# Sidekick_Breakout_V1_2_LDO.net
KiCad netlist of a schematic drawn in EasyEDA
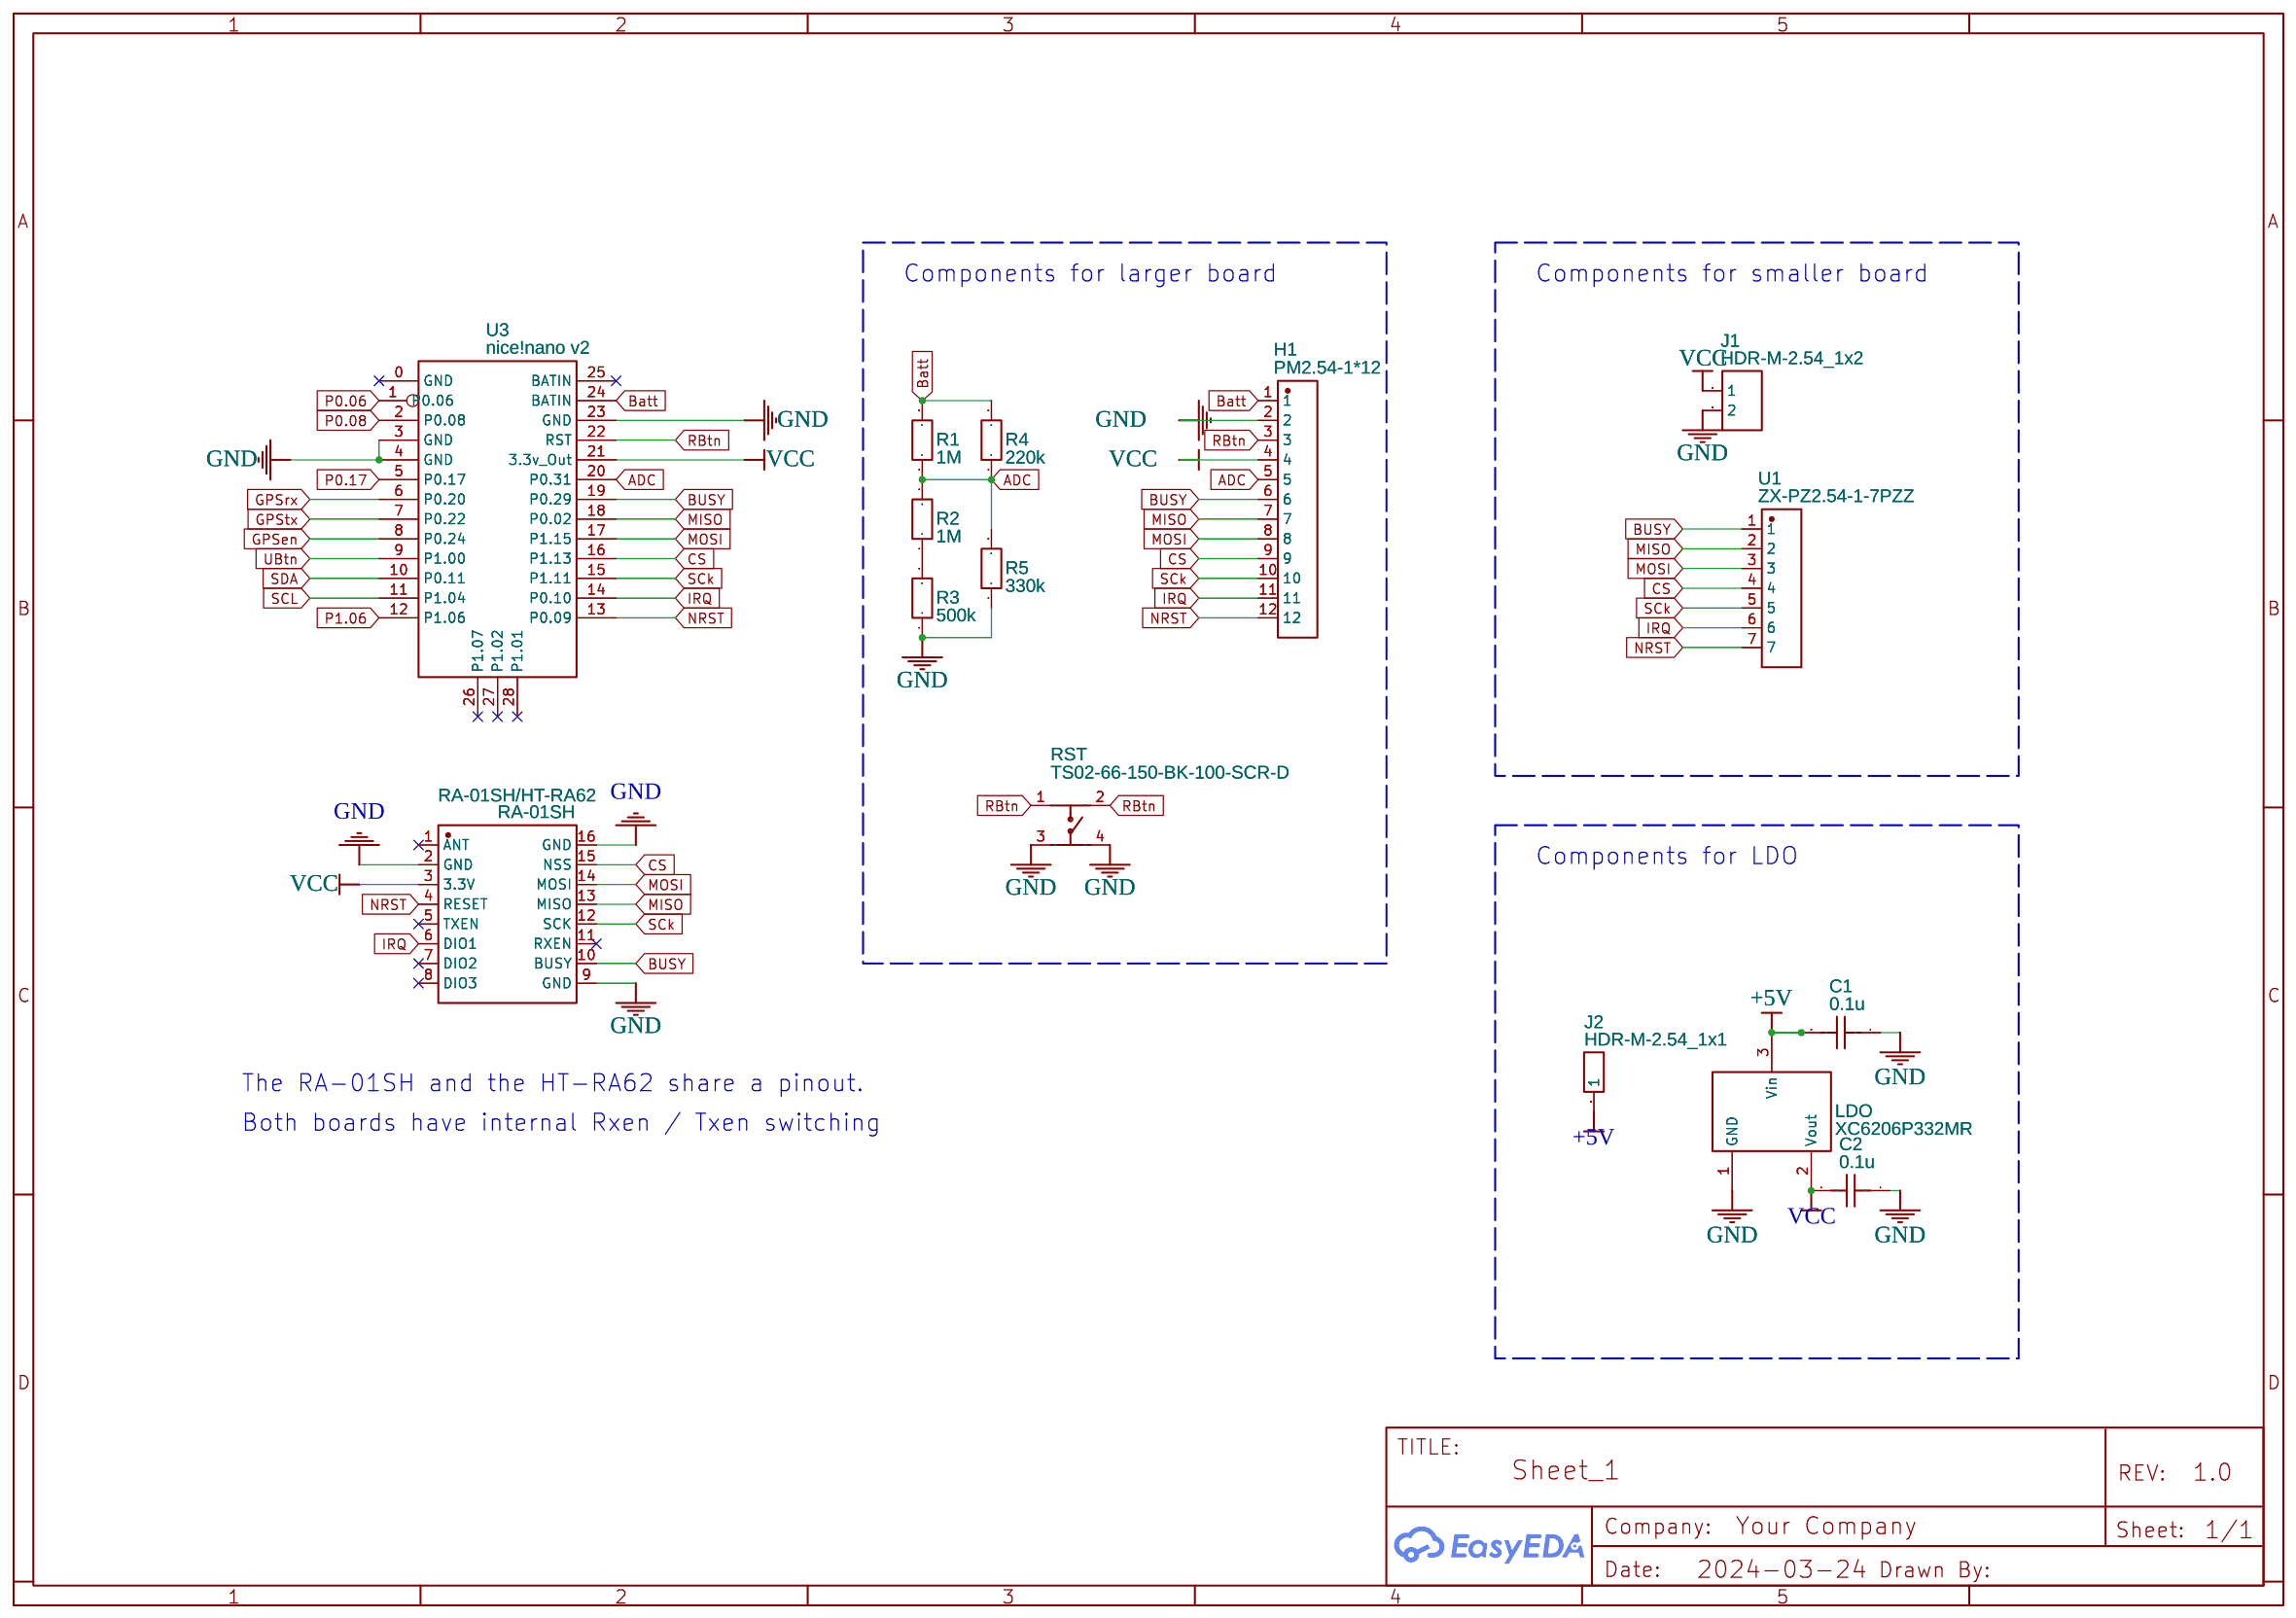
[diagram p0: schematic sheet]

(export (version "E")
  (design (tool "Eeschema 10.0.6"))
  (components
    (comp (ref "C1") (value "0.1u") (libsource (lib "") (part "C_0805_US")))
    (comp (ref "C2") (value "0.1u") (libsource (lib "") (part "C_0805_US")))
    (comp (ref "H1")
      (value "PM2.54-1*12")
      (fields (field (name "Manufacturer") "ZHOURI(洲日)"))
      (libsource (lib "") (part "PM2.54-1*12"))
    )
    (comp (ref "J1") (value "HDR-M-2.54_1x2") (libsource (lib "") (part "HDR-M-2.54_1x2")))
    (comp (ref "J2") (value "HDR-M-2.54_1x1") (libsource (lib "") (part "HDR-M-2.54_1x1")))
    (comp (ref "LDO")
      (value "XC6206P332MR")
      (fields (field (name "Manufacturer Part") "XC6206P332MR-G") (field (name "Manufacturer") "TOREX(特瑞仕)"))
      (libsource (lib "") (part "XC6206P332MR"))
    )
    (comp (ref "R1") (value "1M") (libsource (lib "") (part "R_1206_EU")))
    (comp (ref "R2") (value "1M") (libsource (lib "") (part "R_1206_EU")))
    (comp (ref "R3") (value "500k") (libsource (lib "") (part "R_1206_EU")))
    (comp (ref "R4") (value "220k") (libsource (lib "") (part "R_AXIAL-0.3_EU")))
    (comp (ref "R5") (value "330k") (libsource (lib "") (part "R_AXIAL-0.3_EU")))
    (comp (ref "RA-01SH/HT-RA62")
      (value "RA-01SH")
      (fields (field (name "Manufacturer Part") "Ra-01SH") (field (name "Manufacturer") "Ai-Thinker(安信可)"))
      (libsource (lib "") (part "RA-01SH"))
    )
    (comp (ref "RST")
      (value "TS02-66-150-BK-100-SCR-D")
      (fields (field (name "Manufacturer") "CUI"))
      (libsource (lib "") (part "TS02-66-150-BK-100-SCR-D"))
    )
    (comp (ref "U1")
      (value "ZX-PZ2.54-1-7PZZ")
      (fields (field (name "Manufacturer") "Megastar(兆星)"))
      (libsource (lib "") (part "ZX-PZ2.54-1-7PZZ"))
    )
    (comp (ref "U3")
      (value "nice!nano v2")
      (fields (field (name "Manufacturer") "nice!"))
      (libsource (lib "") (part "nice!nano v2"))
    )
  )
  (nets
    (net (code "1") (name "+5V") (class "Default")
      (node (ref "C1") (pin "2") (pinfunction "2_2") (pintype "unspecified"))
      (node (ref "J2") (pin "1") (pinfunction "1_1") (pintype "input"))
      (node (ref "LDO") (pin "3") (pinfunction "Vin_3") (pintype "unspecified"))
    )
    (net (code "2") (name "ADC") (class "Default")
      (node (ref "H1") (pin "5") (pinfunction "5_5") (pintype "unspecified"))
      (node (ref "R1") (pin "1") (pinfunction "1_1") (pintype "unspecified"))
      (node (ref "R2") (pin "2") (pinfunction "2_2") (pintype "unspecified"))
      (node (ref "R4") (pin "1") (pinfunction "1_1") (pintype "unspecified"))
      (node (ref "R5") (pin "2") (pinfunction "2_2") (pintype "unspecified"))
      (node (ref "U3") (pin "20") (pinfunction "P0.31_20") (pintype "bidirectional"))
    )
    (net (code "3") (name "BUSY") (class "Default")
      (node (ref "H1") (pin "6") (pinfunction "6_6") (pintype "unspecified"))
      (node (ref "RA-01SH/HT-RA62") (pin "10") (pinfunction "BUSY_10") (pintype "unspecified"))
      (node (ref "U1") (pin "1") (pinfunction "1_1") (pintype "unspecified"))
      (node (ref "U3") (pin "19") (pinfunction "P0.29_19") (pintype "bidirectional"))
    )
    (net (code "4") (name "Batt") (class "Default")
      (node (ref "H1") (pin "1") (pinfunction "1_1") (pintype "unspecified"))
      (node (ref "R1") (pin "2") (pinfunction "2_2") (pintype "unspecified"))
      (node (ref "R4") (pin "2") (pinfunction "2_2") (pintype "unspecified"))
      (node (ref "U3") (pin "24") (pinfunction "BATIN_24") (pintype "bidirectional"))
    )
    (net (code "5") (name "CS") (class "Default")
      (node (ref "H1") (pin "9") (pinfunction "9_9") (pintype "unspecified"))
      (node (ref "RA-01SH/HT-RA62") (pin "15") (pinfunction "NSS_15") (pintype "unspecified"))
      (node (ref "U1") (pin "4") (pinfunction "4_4") (pintype "unspecified"))
      (node (ref "U3") (pin "16") (pinfunction "P1.13_16") (pintype "bidirectional"))
    )
    (net (code "6") (name "GND") (class "Default")
      (node (ref "C1") (pin "1") (pinfunction "1_1") (pintype "unspecified"))
      (node (ref "C2") (pin "1") (pinfunction "1_1") (pintype "unspecified"))
      (node (ref "H1") (pin "2") (pinfunction "2_2") (pintype "unspecified"))
      (node (ref "J1") (pin "2") (pinfunction "2_2") (pintype "unspecified"))
      (node (ref "LDO") (pin "1") (pinfunction "GND_1") (pintype "unspecified"))
      (node (ref "R3") (pin "1") (pinfunction "1_1") (pintype "unspecified"))
      (node (ref "R5") (pin "1") (pinfunction "1_1") (pintype "unspecified"))
      (node (ref "RA-01SH/HT-RA62") (pin "16") (pinfunction "GND_16") (pintype "unspecified"))
      (node (ref "RA-01SH/HT-RA62") (pin "2") (pinfunction "GND_2") (pintype "unspecified"))
      (node (ref "RA-01SH/HT-RA62") (pin "9") (pinfunction "GND_9") (pintype "unspecified"))
      (node (ref "RST") (pin "3") (pinfunction "3_3") (pintype "unspecified"))
      (node (ref "RST") (pin "4") (pinfunction "4_4") (pintype "unspecified"))
      (node (ref "U3") (pin "23") (pinfunction "GND_23") (pintype "bidirectional"))
      (node (ref "U3") (pin "3") (pinfunction "GND_3") (pintype "unspecified"))
      (node (ref "U3") (pin "4") (pinfunction "GND_4") (pintype "unspecified"))
    )
    (net (code "7") (name "GPSen") (class "Default")
      (node (ref "U3") (pin "8") (pinfunction "P0.24_8") (pintype "unspecified"))
    )
    (net (code "8") (name "GPSrx") (class "Default")
      (node (ref "U3") (pin "6") (pinfunction "P0.20_6") (pintype "unspecified"))
    )
    (net (code "9") (name "GPStx") (class "Default")
      (node (ref "U3") (pin "7") (pinfunction "P0.22_7") (pintype "unspecified"))
    )
    (net (code "10") (name "IRQ") (class "Default")
      (node (ref "H1") (pin "11") (pinfunction "11_11") (pintype "unspecified"))
      (node (ref "RA-01SH/HT-RA62") (pin "6") (pinfunction "DIO1_6") (pintype "unspecified"))
      (node (ref "U1") (pin "6") (pinfunction "6_6") (pintype "unspecified"))
      (node (ref "U3") (pin "14") (pinfunction "P0.10_14") (pintype "bidirectional"))
    )
    (net (code "11") (name "MISO") (class "Default")
      (node (ref "H1") (pin "7") (pinfunction "7_7") (pintype "unspecified"))
      (node (ref "RA-01SH/HT-RA62") (pin "13") (pinfunction "MISO_13") (pintype "unspecified"))
      (node (ref "U1") (pin "2") (pinfunction "2_2") (pintype "unspecified"))
      (node (ref "U3") (pin "18") (pinfunction "P0.02_18") (pintype "bidirectional"))
    )
    (net (code "12") (name "MOSI") (class "Default")
      (node (ref "H1") (pin "8") (pinfunction "8_8") (pintype "unspecified"))
      (node (ref "RA-01SH/HT-RA62") (pin "14") (pinfunction "MOSI_14") (pintype "unspecified"))
      (node (ref "U1") (pin "3") (pinfunction "3_3") (pintype "unspecified"))
      (node (ref "U3") (pin "17") (pinfunction "P1.15_17") (pintype "bidirectional"))
    )
    (net (code "13") (name "NRST") (class "Default")
      (node (ref "H1") (pin "12") (pinfunction "12_12") (pintype "unspecified"))
      (node (ref "RA-01SH/HT-RA62") (pin "4") (pinfunction "RESET_4") (pintype "unspecified"))
      (node (ref "U1") (pin "7") (pinfunction "7_7") (pintype "unspecified"))
      (node (ref "U3") (pin "13") (pinfunction "P0.09_13") (pintype "bidirectional"))
    )
    (net (code "14") (name "Net-(R2-Pad1)") (class "Default")
      (node (ref "R2") (pin "1") (pinfunction "1_1") (pintype "unspecified"))
      (node (ref "R3") (pin "2") (pinfunction "2_2") (pintype "unspecified"))
    )
    (net (code "15") (name "P0.06") (class "Default")
      (node (ref "U3") (pin "1") (pinfunction "P0.06_1") (pintype "input"))
    )
    (net (code "16") (name "P0.08") (class "Default")
      (node (ref "U3") (pin "2") (pinfunction "P0.08_2") (pintype "input"))
    )
    (net (code "17") (name "P0.17") (class "Default")
      (node (ref "U3") (pin "5") (pinfunction "P0.17_5") (pintype "unspecified"))
    )
    (net (code "18") (name "P1.06") (class "Default")
      (node (ref "U3") (pin "12") (pinfunction "P1.06_12") (pintype "unspecified"))
    )
    (net (code "19") (name "RBtn") (class "Default")
      (node (ref "H1") (pin "3") (pinfunction "3_3") (pintype "unspecified"))
      (node (ref "RST") (pin "1") (pinfunction "1_1") (pintype "unspecified"))
      (node (ref "RST") (pin "2") (pinfunction "2_2") (pintype "unspecified"))
      (node (ref "U3") (pin "22") (pinfunction "RST_22") (pintype "bidirectional"))
    )
    (net (code "20") (name "SCL") (class "Default")
      (node (ref "U3") (pin "11") (pinfunction "P1.04_11") (pintype "unspecified"))
    )
    (net (code "21") (name "SCk") (class "Default")
      (node (ref "H1") (pin "10") (pinfunction "10_10") (pintype "unspecified"))
      (node (ref "RA-01SH/HT-RA62") (pin "12") (pinfunction "SCK_12") (pintype "unspecified"))
      (node (ref "U1") (pin "5") (pinfunction "5_5") (pintype "unspecified"))
      (node (ref "U3") (pin "15") (pinfunction "P1.11_15") (pintype "bidirectional"))
    )
    (net (code "22") (name "SDA") (class "Default")
      (node (ref "U3") (pin "10") (pinfunction "P0.11_10") (pintype "unspecified"))
    )
    (net (code "23") (name "UBtn") (class "Default")
      (node (ref "U3") (pin "9") (pinfunction "P1.00_9") (pintype "unspecified"))
    )
    (net (code "24") (name "VCC") (class "Default")
      (node (ref "C2") (pin "2") (pinfunction "2_2") (pintype "unspecified"))
      (node (ref "H1") (pin "4") (pinfunction "4_4") (pintype "unspecified"))
      (node (ref "J1") (pin "1") (pinfunction "1_1") (pintype "unspecified"))
      (node (ref "LDO") (pin "2") (pinfunction "Vout_2") (pintype "unspecified"))
      (node (ref "RA-01SH/HT-RA62") (pin "3") (pinfunction "3.3V_3") (pintype "unspecified"))
      (node (ref "U3") (pin "21") (pinfunction "3.3v_Out_21") (pintype "bidirectional"))
    )
    (net (code "25") (name "unconnected-(RA-01SH/HT-RA62-ANT-Pad1)") (class "Default")
      (node (ref "RA-01SH/HT-RA62") (pin "1") (pinfunction "ANT_1") (pintype "unspecified+no_connect"))
    )
    (net (code "26") (name "unconnected-(RA-01SH/HT-RA62-DIO2-Pad7)") (class "Default")
      (node (ref "RA-01SH/HT-RA62") (pin "7") (pinfunction "DIO2_7") (pintype "unspecified+no_connect"))
    )
    (net (code "27") (name "unconnected-(RA-01SH/HT-RA62-DIO3-Pad8)") (class "Default")
      (node (ref "RA-01SH/HT-RA62") (pin "8") (pinfunction "DIO3_8") (pintype "unspecified+no_connect"))
    )
    (net (code "28") (name "unconnected-(RA-01SH/HT-RA62-RXEN-Pad11)") (class "Default")
      (node (ref "RA-01SH/HT-RA62") (pin "11") (pinfunction "RXEN_11") (pintype "unspecified+no_connect"))
    )
    (net (code "29") (name "unconnected-(RA-01SH/HT-RA62-TXEN-Pad5)") (class "Default")
      (node (ref "RA-01SH/HT-RA62") (pin "5") (pinfunction "TXEN_5") (pintype "unspecified+no_connect"))
    )
    (net (code "30") (name "unconnected-(U3-BATIN-Pad25)") (class "Default")
      (node (ref "U3") (pin "25") (pinfunction "BATIN_25") (pintype "bidirectional+no_connect"))
    )
    (net (code "31") (name "unconnected-(U3-GND-Pad0)") (class "Default")
      (node (ref "U3") (pin "0") (pinfunction "GND_0") (pintype "unspecified+no_connect"))
    )
    (net (code "32") (name "unconnected-(U3-P1.01-Pad28)") (class "Default")
      (node (ref "U3") (pin "28") (pinfunction "P1.01_28") (pintype "unspecified+no_connect"))
    )
    (net (code "33") (name "unconnected-(U3-P1.02-Pad27)") (class "Default")
      (node (ref "U3") (pin "27") (pinfunction "P1.02_27") (pintype "unspecified+no_connect"))
    )
    (net (code "34") (name "unconnected-(U3-P1.07-Pad26)") (class "Default")
      (node (ref "U3") (pin "26") (pinfunction "P1.07_26") (pintype "unspecified+no_connect"))
    )
  )
)
